# dc25-darknet-dialer-eaglev8.net
KiCad netlist of a schematic drawn in EAGLE
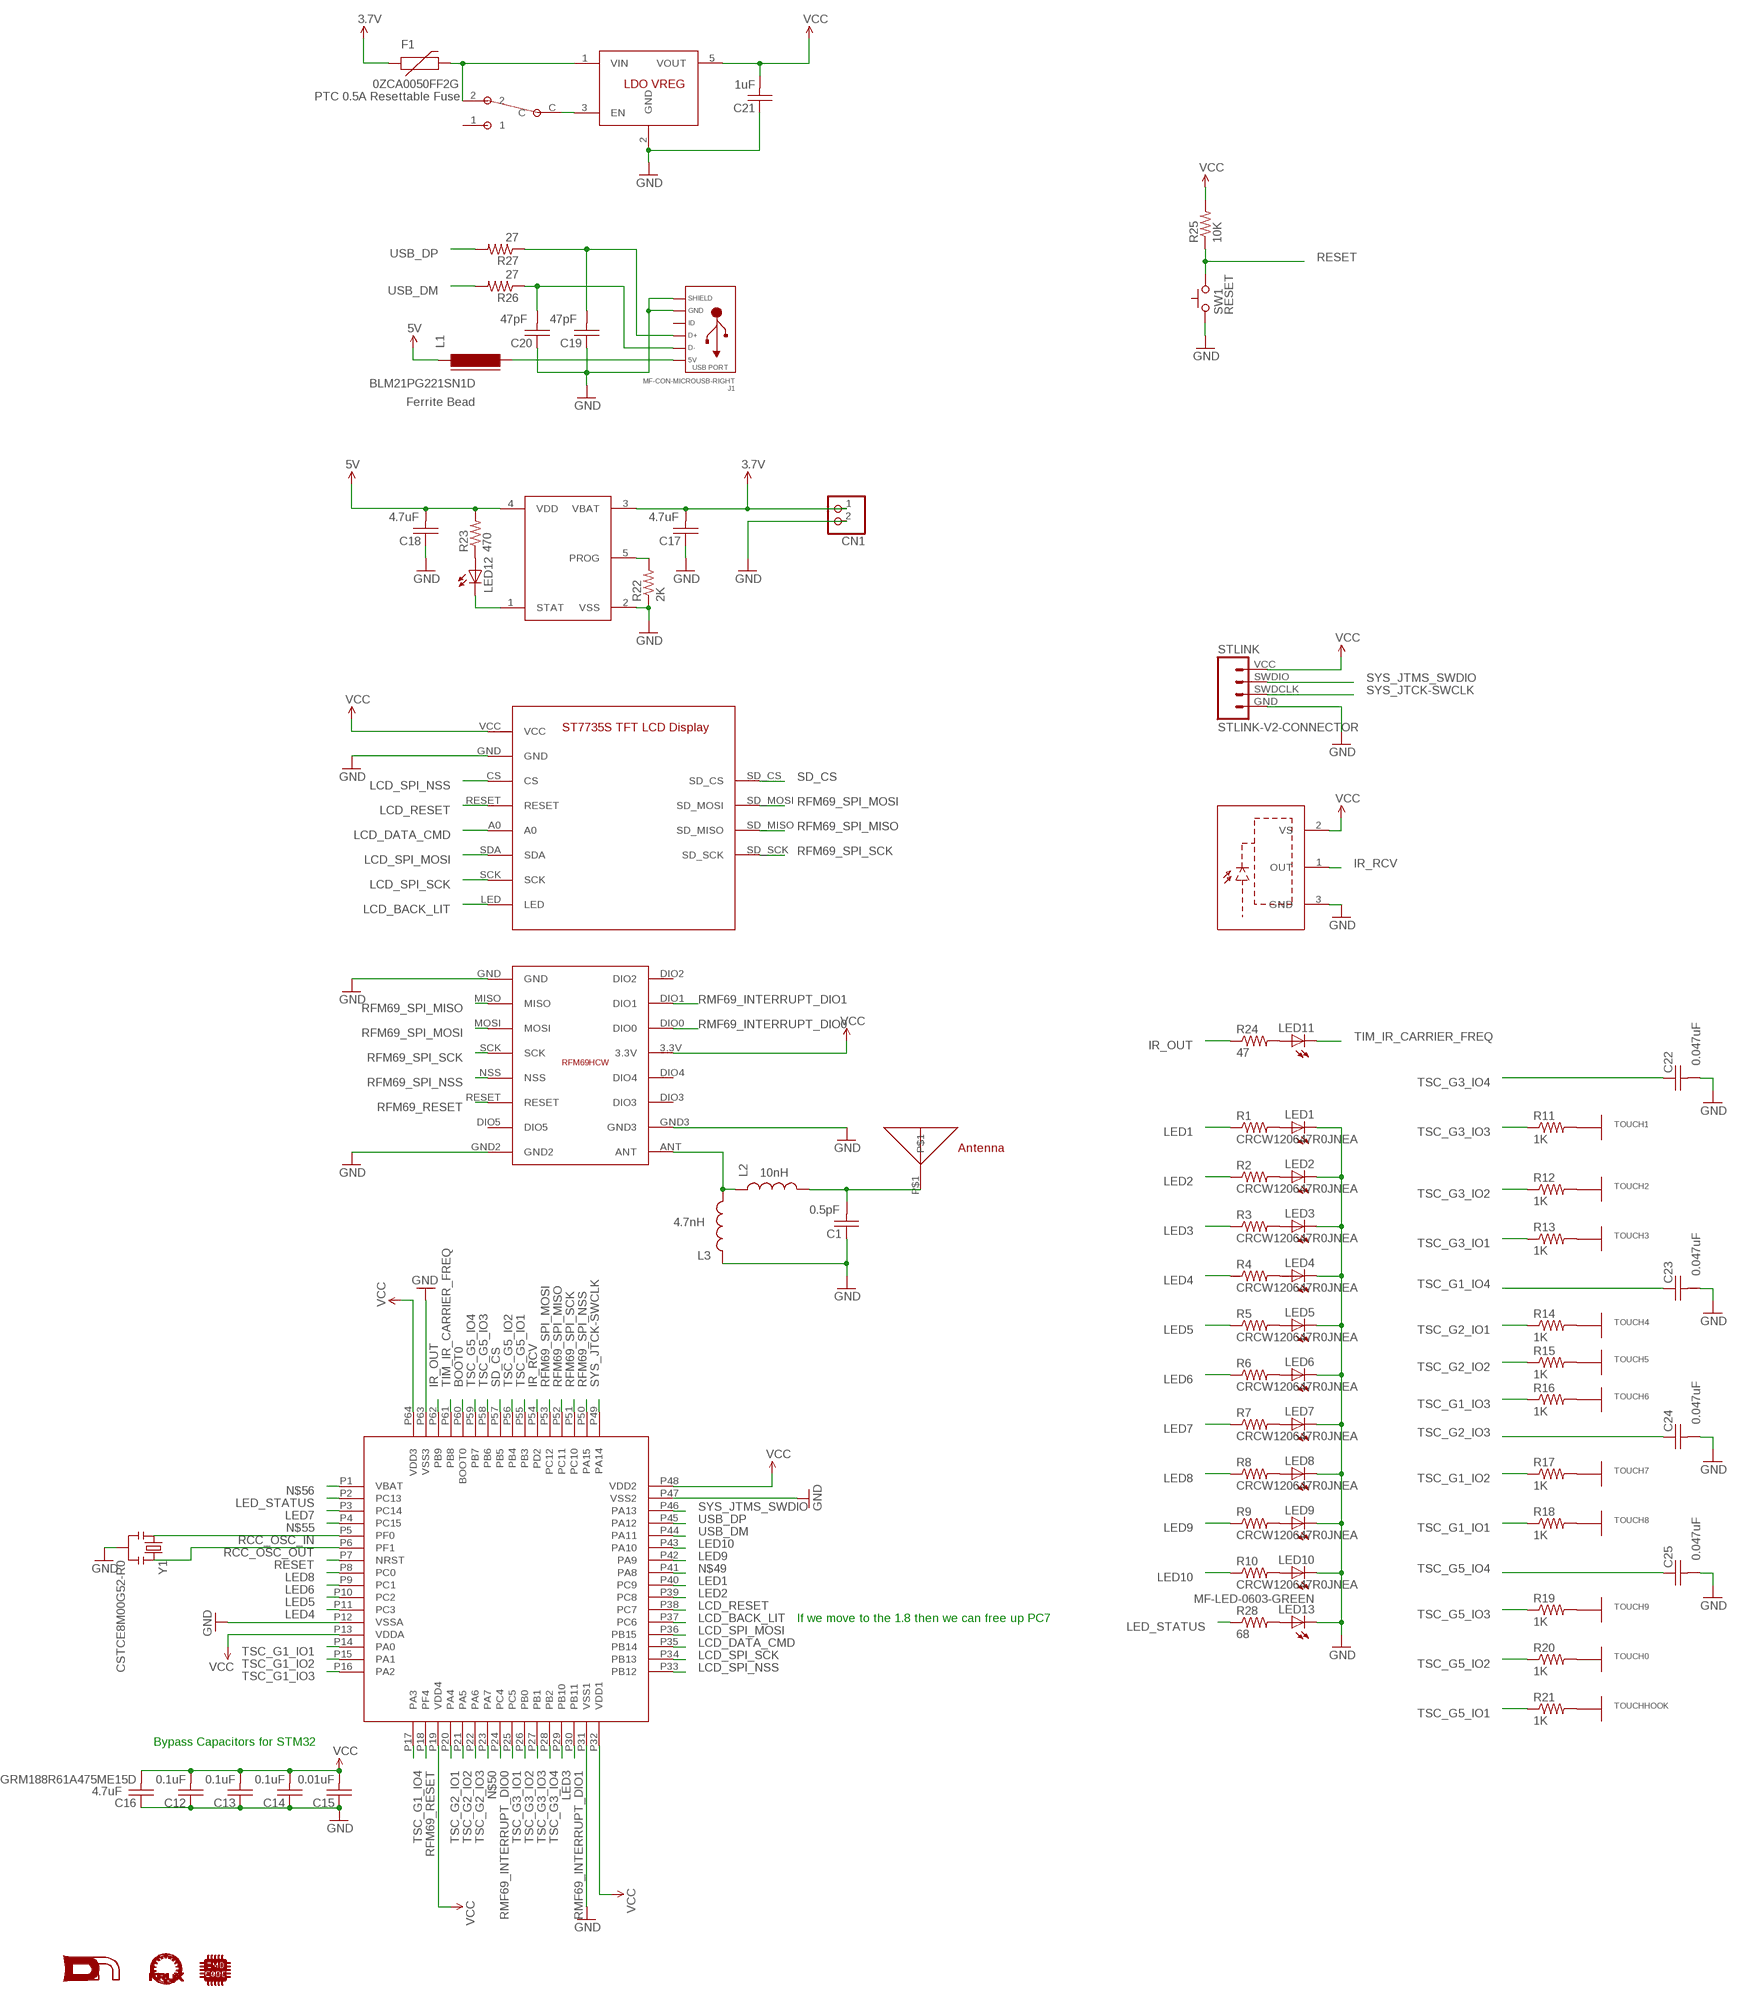
[diagram p0: schematic, sheet 1]

(export (version "E")
  (design (tool "Eeschema 10.0.6"))
  (components
    (comp (ref "C1")
      (value "251R14S0R5BV4T")
      (footprint "eagle-import:C0603")
      (libsource (lib "eagle-import") (part "C-USC0603"))
    )
    (comp (ref "C12")
      (value "0.1uF")
      (footprint "eagle-import:C0603")
      (libsource (lib "eagle-import") (part "C-USC0603"))
    )
    (comp (ref "C13")
      (value "0.1uF")
      (footprint "eagle-import:C0603")
      (libsource (lib "eagle-import") (part "C-USC0603"))
    )
    (comp (ref "C14")
      (value "0.1uF")
      (footprint "eagle-import:C0603")
      (libsource (lib "eagle-import") (part "C-USC0603"))
    )
    (comp (ref "C15")
      (value "0.01uF")
      (footprint "eagle-import:C0603")
      (libsource (lib "eagle-import") (part "C-USC0603"))
    )
    (comp (ref "C16")
      (value "GRM188R61A475ME15D")
      (footprint "eagle-import:C0603")
      (libsource (lib "eagle-import") (part "C-USC0603"))
    )
    (comp (ref "C17")
      (value "GRM188R61A475ME15D")
      (footprint "eagle-import:C0603")
      (libsource (lib "eagle-import") (part "C-USC0603"))
    )
    (comp (ref "C18")
      (value "GRM188R61A475ME15D")
      (footprint "eagle-import:C0603")
      (libsource (lib "eagle-import") (part "C-USC0603"))
    )
    (comp (ref "C19")
      (value "C0603C470J3GACTU")
      (footprint "eagle-import:C0603")
      (libsource (lib "eagle-import") (part "C-USC0603"))
    )
    (comp (ref "C20")
      (value "C0603C470J3GACTU")
      (footprint "eagle-import:C0603")
      (libsource (lib "eagle-import") (part "C-USC0603"))
    )
    (comp (ref "C21")
      (value "1uF")
      (footprint "eagle-import:C0603")
      (libsource (lib "eagle-import") (part "C-USC0603"))
    )
    (comp (ref "C22")
      (value "C0603C473J3RACAUTO")
      (footprint "eagle-import:C0603")
      (libsource (lib "eagle-import") (part "C-USC0603"))
    )
    (comp (ref "C23")
      (value "C0603C473J3RACAUTO")
      (footprint "eagle-import:C0603")
      (libsource (lib "eagle-import") (part "C-USC0603"))
    )
    (comp (ref "C24")
      (value "C0603C473J3RACAUTO")
      (footprint "eagle-import:C0603")
      (libsource (lib "eagle-import") (part "C-USC0603"))
    )
    (comp (ref "C25")
      (value "C0603C473J3RACAUTO")
      (footprint "eagle-import:C0603")
      (libsource (lib "eagle-import") (part "C-USC0603"))
    )
    (comp (ref "CN1")
      (value "JST_2PIN-THM-RA")
      (footprint "eagle-import:JST-PH-2-THM-RA")
      (libsource (lib "eagle-import") (part "JST_2PIN-THM-RA"))
    )
    (comp (ref "F1")
      (value "0ZCA0050FF2G")
      (footprint "eagle-import:PTC-1206")
      (libsource (lib "eagle-import") (part "PTCSMD"))
    )
    (comp (ref "J1")
      (value "MF-CON-MICROUSB-RIGHT")
      (footprint "eagle-import:MICROUSB-RIGHT")
      (fields (field (name "HOUSEPART") "YES"))
      (libsource (lib "eagle-import") (part "USB_MICRO_RIGHT"))
    )
    (comp (ref "L1")
      (value "BLM21PG221SN1D")
      (footprint "eagle-import:FB603")
      (libsource (lib "eagle-import") (part "FERRITE-0603"))
    )
    (comp (ref "L2")
      (value "CI160808-10NJ")
      (footprint "eagle-import:0603")
      (libsource (lib "eagle-import") (part "INDUCTOR0603"))
    )
    (comp (ref "L3")
      (value "CI160808-4N7D")
      (footprint "eagle-import:0603")
      (libsource (lib "eagle-import") (part "INDUCTOR0603"))
    )
    (comp (ref "LED1")
      (value "LEDREVERSEMOUNT")
      (footprint "eagle-import:GULLWING_LED")
      (libsource (lib "eagle-import") (part "LEDREVERSEMOUNT"))
    )
    (comp (ref "LED2")
      (value "LEDREVERSEMOUNT")
      (footprint "eagle-import:GULLWING_LED")
      (libsource (lib "eagle-import") (part "LEDREVERSEMOUNT"))
    )
    (comp (ref "LED3")
      (value "LEDREVERSEMOUNT")
      (footprint "eagle-import:GULLWING_LED")
      (libsource (lib "eagle-import") (part "LEDREVERSEMOUNT"))
    )
    (comp (ref "LED4")
      (value "LEDREVERSEMOUNT")
      (footprint "eagle-import:GULLWING_LED")
      (libsource (lib "eagle-import") (part "LEDREVERSEMOUNT"))
    )
    (comp (ref "LED5")
      (value "LEDREVERSEMOUNT")
      (footprint "eagle-import:GULLWING_LED")
      (libsource (lib "eagle-import") (part "LEDREVERSEMOUNT"))
    )
    (comp (ref "LED6")
      (value "LEDREVERSEMOUNT")
      (footprint "eagle-import:GULLWING_LED")
      (libsource (lib "eagle-import") (part "LEDREVERSEMOUNT"))
    )
    (comp (ref "LED7")
      (value "LEDREVERSEMOUNT")
      (footprint "eagle-import:GULLWING_LED")
      (libsource (lib "eagle-import") (part "LEDREVERSEMOUNT"))
    )
    (comp (ref "LED8")
      (value "LEDREVERSEMOUNT")
      (footprint "eagle-import:GULLWING_LED")
      (libsource (lib "eagle-import") (part "LEDREVERSEMOUNT"))
    )
    (comp (ref "LED9")
      (value "LEDREVERSEMOUNT")
      (footprint "eagle-import:GULLWING_LED")
      (libsource (lib "eagle-import") (part "LEDREVERSEMOUNT"))
    )
    (comp (ref "LED10")
      (value "LEDREVERSEMOUNT")
      (footprint "eagle-import:GULLWING_LED")
      (libsource (lib "eagle-import") (part "LEDREVERSEMOUNT"))
    )
    (comp (ref "LED11")
      (value "LED5MM")
      (footprint "eagle-import:LED5MM")
      (libsource (lib "eagle-import") (part "LED5MM"))
    )
    (comp (ref "LED12")
      (value "MF-LED-0603-GREEN")
      (footprint "eagle-import:LED-0603")
      (libsource (lib "eagle-import") (part "LED0603"))
    )
    (comp (ref "LED13")
      (value "MF-LED-0603-GREEN")
      (footprint "eagle-import:LED-0603")
      (libsource (lib "eagle-import") (part "LED0603"))
    )
    (comp (ref "R1")
      (value "CRCW120647R0JNEA")
      (footprint "eagle-import:1206")
      (libsource (lib "eagle-import") (part "RESISTOR1206"))
    )
    (comp (ref "R2")
      (value "CRCW120647R0JNEA")
      (footprint "eagle-import:1206")
      (libsource (lib "eagle-import") (part "RESISTOR1206"))
    )
    (comp (ref "R3")
      (value "CRCW120647R0JNEA")
      (footprint "eagle-import:1206")
      (libsource (lib "eagle-import") (part "RESISTOR1206"))
    )
    (comp (ref "R4")
      (value "CRCW120647R0JNEA")
      (footprint "eagle-import:1206")
      (libsource (lib "eagle-import") (part "RESISTOR1206"))
    )
    (comp (ref "R5")
      (value "CRCW120647R0JNEA")
      (footprint "eagle-import:1206")
      (libsource (lib "eagle-import") (part "RESISTOR1206"))
    )
    (comp (ref "R6")
      (value "CRCW120647R0JNEA")
      (footprint "eagle-import:1206")
      (libsource (lib "eagle-import") (part "RESISTOR1206"))
    )
    (comp (ref "R7")
      (value "CRCW120647R0JNEA")
      (footprint "eagle-import:1206")
      (libsource (lib "eagle-import") (part "RESISTOR1206"))
    )
    (comp (ref "R8")
      (value "CRCW120647R0JNEA")
      (footprint "eagle-import:1206")
      (libsource (lib "eagle-import") (part "RESISTOR1206"))
    )
    (comp (ref "R9")
      (value "CRCW120647R0JNEA")
      (footprint "eagle-import:1206")
      (libsource (lib "eagle-import") (part "RESISTOR1206"))
    )
    (comp (ref "R10")
      (value "CRCW120647R0JNEA")
      (footprint "eagle-import:1206")
      (libsource (lib "eagle-import") (part "RESISTOR1206"))
    )
    (comp (ref "R11")
      (value "1K")
      (footprint "eagle-import:0603-RES")
      (libsource (lib "eagle-import") (part "RESISTOR0603-RES"))
    )
    (comp (ref "R12")
      (value "1K")
      (footprint "eagle-import:0603-RES")
      (libsource (lib "eagle-import") (part "RESISTOR0603-RES"))
    )
    (comp (ref "R13")
      (value "1K")
      (footprint "eagle-import:0603-RES")
      (libsource (lib "eagle-import") (part "RESISTOR0603-RES"))
    )
    (comp (ref "R14")
      (value "1K")
      (footprint "eagle-import:0603-RES")
      (libsource (lib "eagle-import") (part "RESISTOR0603-RES"))
    )
    (comp (ref "R15")
      (value "1K")
      (footprint "eagle-import:0603-RES")
      (libsource (lib "eagle-import") (part "RESISTOR0603-RES"))
    )
    (comp (ref "R16")
      (value "1K")
      (footprint "eagle-import:0603-RES")
      (libsource (lib "eagle-import") (part "RESISTOR0603-RES"))
    )
    (comp (ref "R17")
      (value "1K")
      (footprint "eagle-import:0603-RES")
      (libsource (lib "eagle-import") (part "RESISTOR0603-RES"))
    )
    (comp (ref "R18")
      (value "1K")
      (footprint "eagle-import:0603-RES")
      (libsource (lib "eagle-import") (part "RESISTOR0603-RES"))
    )
    (comp (ref "R19")
      (value "1K")
      (footprint "eagle-import:0603-RES")
      (libsource (lib "eagle-import") (part "RESISTOR0603-RES"))
    )
    (comp (ref "R20")
      (value "1K")
      (footprint "eagle-import:0603-RES")
      (libsource (lib "eagle-import") (part "RESISTOR0603-RES"))
    )
    (comp (ref "R21")
      (value "1K")
      (footprint "eagle-import:0603-RES")
      (libsource (lib "eagle-import") (part "RESISTOR0603-RES"))
    )
    (comp (ref "R22")
      (value "2K")
      (footprint "eagle-import:0603-RES")
      (libsource (lib "eagle-import") (part "RESISTOR0603-RES"))
    )
    (comp (ref "R23")
      (value "470")
      (footprint "eagle-import:0603-RES")
      (libsource (lib "eagle-import") (part "RESISTOR0603-RES"))
    )
    (comp (ref "R24")
      (value "47")
      (footprint "eagle-import:0207_7")
      (libsource (lib "eagle-import") (part "R-US_0207/7"))
    )
    (comp (ref "R25")
      (value "10K")
      (footprint "eagle-import:0603-RES")
      (libsource (lib "eagle-import") (part "RESISTOR0603-RES"))
    )
    (comp (ref "R26")
      (value "27")
      (footprint "eagle-import:0603-RES")
      (libsource (lib "eagle-import") (part "RESISTOR0603-RES"))
    )
    (comp (ref "R27")
      (value "27")
      (footprint "eagle-import:0603-RES")
      (libsource (lib "eagle-import") (part "RESISTOR0603-RES"))
    )
    (comp (ref "R28")
      (value "68")
      (footprint "eagle-import:0603-RES")
      (libsource (lib "eagle-import") (part "RESISTOR0603-RES"))
    )
    (comp (ref "STLINK")
      (value "STLINK-V2-CONNECTOR")
      (footprint "eagle-import:1X04")
      (libsource (lib "eagle-import") (part "STLINK-V2-CONNECTOR"))
    )
    (comp (ref "SW1")
      (value "RESET")
      (footprint "eagle-import:TACTILE-2PIN-NARROW")
      (libsource (lib "eagle-import") (part "SWITCH_TACTILETACTILE-2PIN-NARROW"))
    )
    (comp (ref "TOUCH0")
      (value "CAP_TOUCH0")
      (footprint "eagle-import:CAP_TOUCH_PAD_0")
      (libsource (lib "eagle-import") (part "CAP_TOUCH0"))
    )
    (comp (ref "TOUCH1")
      (value "CAP_TOUCH1")
      (footprint "eagle-import:CAP_TOUCH_PAD_1")
      (libsource (lib "eagle-import") (part "CAP_TOUCH1"))
    )
    (comp (ref "TOUCH2")
      (value "CAP_TOUCH2")
      (footprint "eagle-import:CAP_TOUCH_PAD_2")
      (libsource (lib "eagle-import") (part "CAP_TOUCH2"))
    )
    (comp (ref "TOUCH3")
      (value "CAP_TOUCH3")
      (footprint "eagle-import:CAP_TOUCH_PAD_3")
      (libsource (lib "eagle-import") (part "CAP_TOUCH3"))
    )
    (comp (ref "TOUCH4")
      (value "CAP_TOUCH4")
      (footprint "eagle-import:CAP_TOUCH_PAD_4")
      (libsource (lib "eagle-import") (part "CAP_TOUCH4"))
    )
    (comp (ref "TOUCH5")
      (value "CAP_TOUCH5")
      (footprint "eagle-import:CAP_TOUCH_PAD_5")
      (libsource (lib "eagle-import") (part "CAP_TOUCH5"))
    )
    (comp (ref "TOUCH6")
      (value "CAP_TOUCH6")
      (footprint "eagle-import:CAP_TOUCH_PAD_6")
      (libsource (lib "eagle-import") (part "CAP_TOUCH6"))
    )
    (comp (ref "TOUCH7")
      (value "CAP_TOUCH7")
      (footprint "eagle-import:CAP_TOUCH_PAD_7")
      (libsource (lib "eagle-import") (part "CAP_TOUCH7"))
    )
    (comp (ref "TOUCH8")
      (value "CAP_TOUCH8")
      (footprint "eagle-import:CAP_TOUCH_PAD_8")
      (libsource (lib "eagle-import") (part "CAP_TOUCH8"))
    )
    (comp (ref "TOUCH9")
      (value "CAP_TOUCH9")
      (footprint "eagle-import:CAP_TOUCH_PAD_9")
      (libsource (lib "eagle-import") (part "CAP_TOUCH9"))
    )
    (comp (ref "TOUCHHOOK")
      (value "CAP_TOUCHHOOK")
      (footprint "eagle-import:CAP_TOUCH_PAD_HOOK")
      (libsource (lib "eagle-import") (part "CAP_TOUCHHOOK"))
    )
    (comp (ref "U$1")
      (value "DN_LOGO")
      (footprint "eagle-import:DN_LOGO")
      (libsource (lib "eagle-import") (part "DN_LOGO"))
    )
    (comp (ref "U$2")
      (value "STM32F302RBT6")
      (footprint "eagle-import:LQFP64")
      (libsource (lib "eagle-import") (part "STM32F302XC"))
    )
    (comp (ref "U$11")
      (value "SWITCH_SPDT")
      (footprint "eagle-import:SPDT_SSAJ120100")
      (libsource (lib "eagle-import") (part "SWITCH_SPDT"))
    )
    (comp (ref "U$12")
      (value "KRUX_LOGO")
      (footprint "eagle-import:KRUX_LOGO")
      (libsource (lib "eagle-import") (part "KRUX_LOGO"))
    )
    (comp (ref "U$15")
      (value "RFM69HCWRFN69HCWSMD")
      (footprint "eagle-import:16PIN-PCB-SMD")
      (libsource (lib "eagle-import") (part "RFM69HCWRFN69HCWSMD"))
    )
    (comp (ref "U$21")
      (value "0915AT43A0026E")
      (footprint "eagle-import:CHIP_ANTENNA_1.8X8MM")
      (libsource (lib "eagle-import") (part "CHIP_ANTENNA"))
    )
    (comp (ref "U$22")
      (value "ST7735S_LCD_MODULE")
      (footprint "eagle-import:ST7735S_LCD_DISPLAY")
      (libsource (lib "eagle-import") (part "ST7735S_LCD_MODULE"))
    )
    (comp (ref "U$23")
      (value "CMD_C0DE_LOGO")
      (footprint "eagle-import:CMD_C0DE_LOGO")
      (libsource (lib "eagle-import") (part "CMD_C0DE_LOGO"))
    )
    (comp (ref "U1")
      (value "BU33SD5WG-TR")
      (footprint "eagle-import:SOT23-5")
      (libsource (lib "eagle-import") (part "TLV702"))
    )
    (comp (ref "U2")
      (value "MCP73831T-5ACI/OT")
      (footprint "eagle-import:SOT23-5")
      (libsource (lib "eagle-import") (part "DS21984E"))
    )
    (comp (ref "U3")
      (value "SOP22FLAT")
      (footprint "eagle-import:IR-MODULE_FLAT")
      (libsource (lib "eagle-import") (part "SOP22FLAT"))
    )
    (comp (ref "Y1")
      (value "CSTCE8M00G52-R0")
      (footprint "eagle-import:RESONATOR-SMD")
      (libsource (lib "eagle-import") (part "RESONATORSMD"))
    )
  )
  (nets
    (net (code "1") (name "/BOOT0") (class "Default")
      (node (ref "U$2") (pin "P60") (pinfunction "BOOT0_P60") (pintype "bidirectional"))
    )
    (net (code "2") (name "/IR_OUT") (class "Default")
      (node (ref "R24") (pin "1") (pinfunction "1_1") (pintype "passive"))
      (node (ref "U$2") (pin "P62") (pinfunction "PB9_P62") (pintype "bidirectional"))
    )
    (net (code "3") (name "/IR_RCV") (class "Default")
      (node (ref "U$2") (pin "P54") (pinfunction "PD2_P54") (pintype "bidirectional"))
      (node (ref "U3") (pin "1") (pinfunction "OUT_1") (pintype "bidirectional"))
    )
    (net (code "4") (name "/LCD_BACK_LIT") (class "Default")
      (node (ref "U$2") (pin "P37") (pinfunction "PC6_P37") (pintype "bidirectional"))
      (node (ref "U$22") (pin "LED") (pinfunction "LED_LED") (pintype "bidirectional"))
    )
    (net (code "5") (name "/LCD_DATA_CMD") (class "Default")
      (node (ref "U$2") (pin "P35") (pinfunction "PB14_P35") (pintype "bidirectional"))
      (node (ref "U$22") (pin "A0") (pinfunction "A0_A0") (pintype "bidirectional"))
    )
    (net (code "6") (name "/LCD_RESET") (class "Default")
      (node (ref "U$2") (pin "P38") (pinfunction "PC7_P38") (pintype "bidirectional"))
      (node (ref "U$22") (pin "RESET") (pinfunction "RESET_RESET") (pintype "bidirectional"))
    )
    (net (code "7") (name "/LCD_SPI_MOSI") (class "Default")
      (node (ref "U$2") (pin "P36") (pinfunction "PB15_P36") (pintype "bidirectional"))
      (node (ref "U$22") (pin "SDA") (pinfunction "SDA_SDA") (pintype "bidirectional"))
    )
    (net (code "8") (name "/LCD_SPI_NSS") (class "Default")
      (node (ref "U$2") (pin "P33") (pinfunction "PB12_P33") (pintype "bidirectional"))
      (node (ref "U$22") (pin "CS") (pinfunction "CS_CS") (pintype "bidirectional"))
    )
    (net (code "9") (name "/LCD_SPI_SCK") (class "Default")
      (node (ref "U$2") (pin "P34") (pinfunction "PB13_P34") (pintype "bidirectional"))
      (node (ref "U$22") (pin "SCK") (pinfunction "SCK_SCK") (pintype "bidirectional"))
    )
    (net (code "10") (name "/LED1") (class "Default")
      (node (ref "R1") (pin "1") (pinfunction "1_1") (pintype "passive"))
      (node (ref "U$2") (pin "P40") (pinfunction "PC9_P40") (pintype "bidirectional"))
    )
    (net (code "11") (name "/LED2") (class "Default")
      (node (ref "R2") (pin "1") (pinfunction "1_1") (pintype "passive"))
      (node (ref "U$2") (pin "P39") (pinfunction "PC8_P39") (pintype "bidirectional"))
    )
    (net (code "12") (name "/LED3") (class "Default")
      (node (ref "R3") (pin "1") (pinfunction "1_1") (pintype "passive"))
      (node (ref "U$2") (pin "P29") (pinfunction "PB10_P29") (pintype "bidirectional"))
    )
    (net (code "13") (name "/LED4") (class "Default")
      (node (ref "R4") (pin "1") (pinfunction "1_1") (pintype "passive"))
      (node (ref "U$2") (pin "P11") (pinfunction "PC3_P11") (pintype "bidirectional"))
    )
    (net (code "14") (name "/LED5") (class "Default")
      (node (ref "R5") (pin "1") (pinfunction "1_1") (pintype "passive"))
      (node (ref "U$2") (pin "P10") (pinfunction "PC2_P10") (pintype "bidirectional"))
    )
    (net (code "15") (name "/LED6") (class "Default")
      (node (ref "R6") (pin "1") (pinfunction "1_1") (pintype "passive"))
      (node (ref "U$2") (pin "P9") (pinfunction "PC1_P9") (pintype "bidirectional"))
    )
    (net (code "16") (name "/LED7") (class "Default")
      (node (ref "R7") (pin "1") (pinfunction "1_1") (pintype "passive"))
      (node (ref "U$2") (pin "P3") (pinfunction "PC14_P3") (pintype "bidirectional"))
    )
    (net (code "17") (name "/LED8") (class "Default")
      (node (ref "R8") (pin "1") (pinfunction "1_1") (pintype "passive"))
      (node (ref "U$2") (pin "P8") (pinfunction "PC0_P8") (pintype "bidirectional"))
    )
    (net (code "18") (name "/LED9") (class "Default")
      (node (ref "R9") (pin "1") (pinfunction "1_1") (pintype "passive"))
      (node (ref "U$2") (pin "P42") (pinfunction "PA9_P42") (pintype "bidirectional"))
    )
    (net (code "19") (name "/LED10") (class "Default")
      (node (ref "R10") (pin "1") (pinfunction "1_1") (pintype "passive"))
      (node (ref "U$2") (pin "P43") (pinfunction "PA10_P43") (pintype "bidirectional"))
    )
    (net (code "20") (name "/LED_STATUS") (class "Default")
      (node (ref "R28") (pin "1") (pinfunction "1_1") (pintype "passive"))
      (node (ref "U$2") (pin "P2") (pinfunction "PC13_P2") (pintype "bidirectional"))
    )
    (net (code "21") (name "/N$49") (class "Default")
      (node (ref "U$2") (pin "P41") (pinfunction "PA8_P41") (pintype "bidirectional"))
    )
    (net (code "22") (name "/N$50") (class "Default")
      (node (ref "U$2") (pin "P23") (pinfunction "PA7_P23") (pintype "bidirectional"))
    )
    (net (code "23") (name "/N$55") (class "Default")
      (node (ref "U$2") (pin "P4") (pinfunction "PC15_P4") (pintype "bidirectional"))
    )
    (net (code "24") (name "/N$56") (class "Default")
      (node (ref "U$2") (pin "P1") (pinfunction "VBAT_P1") (pintype "bidirectional"))
    )
    (net (code "25") (name "/RCC_OSC_IN") (class "Default")
      (node (ref "U$2") (pin "P5") (pinfunction "PF0_P5") (pintype "bidirectional"))
      (node (ref "Y1") (pin "1") (pinfunction "1_1") (pintype "passive"))
    )
    (net (code "26") (name "/RCC_OSC_OUT") (class "Default")
      (node (ref "U$2") (pin "P6") (pinfunction "PF1_P6") (pintype "bidirectional"))
      (node (ref "Y1") (pin "3") (pinfunction "3_3") (pintype "passive"))
    )
    (net (code "27") (name "/RESET") (class "Default")
      (node (ref "R25") (pin "1") (pinfunction "1_1") (pintype "passive"))
      (node (ref "SW1") (pin "P$1") (pinfunction "A_P$1") (pintype "passive"))
      (node (ref "U$2") (pin "P7") (pinfunction "NRST_P7") (pintype "bidirectional"))
    )
    (net (code "28") (name "/RFM69_RESET") (class "Default")
      (node (ref "U$15") (pin "RESET") (pinfunction "RESET_RESET") (pintype "bidirectional"))
      (node (ref "U$2") (pin "P18") (pinfunction "PF4_P18") (pintype "bidirectional"))
    )
    (net (code "29") (name "/RFM69_SPI_MISO") (class "Default")
      (node (ref "U$15") (pin "MISO") (pinfunction "MISO_MISO") (pintype "bidirectional"))
      (node (ref "U$2") (pin "P52") (pinfunction "PC11_P52") (pintype "bidirectional"))
      (node (ref "U$22") (pin "SD_MISO") (pinfunction "SD_MISO_SD_MISO") (pintype "bidirectional"))
    )
    (net (code "30") (name "/RFM69_SPI_MOSI") (class "Default")
      (node (ref "U$15") (pin "MOSI") (pinfunction "MOSI_MOSI") (pintype "bidirectional"))
      (node (ref "U$2") (pin "P53") (pinfunction "PC12_P53") (pintype "bidirectional"))
      (node (ref "U$22") (pin "SD_MOSI") (pinfunction "SD_MOSI_SD_MOSI") (pintype "bidirectional"))
    )
    (net (code "31") (name "/RFM69_SPI_NSS") (class "Default")
      (node (ref "U$15") (pin "NSS") (pinfunction "NSS_NSS") (pintype "bidirectional"))
      (node (ref "U$2") (pin "P50") (pinfunction "PA15_P50") (pintype "bidirectional"))
    )
    (net (code "32") (name "/RFM69_SPI_SCK") (class "Default")
      (node (ref "U$15") (pin "SCK") (pinfunction "SCK_SCK") (pintype "bidirectional"))
      (node (ref "U$2") (pin "P51") (pinfunction "PC10_P51") (pintype "bidirectional"))
      (node (ref "U$22") (pin "SD_SCK") (pinfunction "SD_SCK_SD_SCK") (pintype "bidirectional"))
    )
    (net (code "33") (name "/RMF69_INTERRUPT_DIO0") (class "Default")
      (node (ref "U$15") (pin "DIO0") (pinfunction "DIO0_DIO0") (pintype "bidirectional"))
      (node (ref "U$2") (pin "P24") (pinfunction "PC4_P24") (pintype "bidirectional"))
    )
    (net (code "34") (name "/RMF69_INTERRUPT_DIO1") (class "Default")
      (node (ref "U$15") (pin "DIO1") (pinfunction "DIO1_DIO1") (pintype "bidirectional"))
      (node (ref "U$2") (pin "P30") (pinfunction "PB11_P30") (pintype "bidirectional"))
    )
    (net (code "35") (name "/SD_CS") (class "Default")
      (node (ref "U$2") (pin "P57") (pinfunction "PB5_P57") (pintype "bidirectional"))
      (node (ref "U$22") (pin "SD_CS") (pinfunction "SD_CS_SD_CS") (pintype "bidirectional"))
    )
    (net (code "36") (name "/SYS_JTCK-SWCLK") (class "Default")
      (node (ref "STLINK") (pin "SWDCLK") (pinfunction "SWDCLK_SWDCLK") (pintype "input"))
      (node (ref "U$2") (pin "P49") (pinfunction "PA14_P49") (pintype "bidirectional"))
    )
    (net (code "37") (name "/SYS_JTMS_SWDIO") (class "Default")
      (node (ref "STLINK") (pin "SWDIO") (pinfunction "SWDIO_SWDIO") (pintype "bidirectional"))
      (node (ref "U$2") (pin "P46") (pinfunction "PA13_P46") (pintype "bidirectional"))
    )
    (net (code "38") (name "/TIM_IR_CARRIER_FREQ") (class "Default")
      (node (ref "LED11") (pin "K") (pinfunction "C_K") (pintype "output"))
      (node (ref "U$2") (pin "P61") (pinfunction "PB8_P61") (pintype "bidirectional"))
    )
    (net (code "39") (name "/TSC_G1_IO1") (class "Default")
      (node (ref "R18") (pin "1") (pinfunction "1_1") (pintype "passive"))
      (node (ref "U$2") (pin "P14") (pinfunction "PA0_P14") (pintype "bidirectional"))
    )
    (net (code "40") (name "/TSC_G1_IO2") (class "Default")
      (node (ref "R17") (pin "1") (pinfunction "1_1") (pintype "passive"))
      (node (ref "U$2") (pin "P15") (pinfunction "PA1_P15") (pintype "bidirectional"))
    )
    (net (code "41") (name "/TSC_G1_IO3") (class "Default")
      (node (ref "R16") (pin "1") (pinfunction "1_1") (pintype "passive"))
      (node (ref "U$2") (pin "P16") (pinfunction "PA2_P16") (pintype "bidirectional"))
    )
    (net (code "42") (name "/TSC_G1_IO4") (class "Default")
      (node (ref "C23") (pin "1") (pinfunction "1_1") (pintype "passive"))
      (node (ref "U$2") (pin "P17") (pinfunction "PA3_P17") (pintype "bidirectional"))
    )
    (net (code "43") (name "/TSC_G2_IO1") (class "Default")
      (node (ref "R14") (pin "1") (pinfunction "1_1") (pintype "passive"))
      (node (ref "U$2") (pin "P20") (pinfunction "PA4_P20") (pintype "bidirectional"))
    )
    (net (code "44") (name "/TSC_G2_IO2") (class "Default")
      (node (ref "R15") (pin "1") (pinfunction "1_1") (pintype "passive"))
      (node (ref "U$2") (pin "P21") (pinfunction "PA5_P21") (pintype "bidirectional"))
    )
    (net (code "45") (name "/TSC_G2_IO3") (class "Default")
      (node (ref "C24") (pin "1") (pinfunction "1_1") (pintype "passive"))
      (node (ref "U$2") (pin "P22") (pinfunction "PA6_P22") (pintype "bidirectional"))
    )
    (net (code "46") (name "/TSC_G3_IO1") (class "Default")
      (node (ref "R13") (pin "1") (pinfunction "1_1") (pintype "passive"))
      (node (ref "U$2") (pin "P25") (pinfunction "PC5_P25") (pintype "bidirectional"))
    )
    (net (code "47") (name "/TSC_G3_IO2") (class "Default")
      (node (ref "R12") (pin "1") (pinfunction "1_1") (pintype "passive"))
      (node (ref "U$2") (pin "P26") (pinfunction "PB0_P26") (pintype "bidirectional"))
    )
    (net (code "48") (name "/TSC_G3_IO3") (class "Default")
      (node (ref "R11") (pin "1") (pinfunction "1_1") (pintype "passive"))
      (node (ref "U$2") (pin "P27") (pinfunction "PB1_P27") (pintype "bidirectional"))
    )
    (net (code "49") (name "/TSC_G3_IO4") (class "Default")
      (node (ref "C22") (pin "1") (pinfunction "1_1") (pintype "passive"))
      (node (ref "U$2") (pin "P28") (pinfunction "PB2_P28") (pintype "bidirectional"))
    )
    (net (code "50") (name "/TSC_G5_IO1") (class "Default")
      (node (ref "R21") (pin "1") (pinfunction "1_1") (pintype "passive"))
      (node (ref "U$2") (pin "P55") (pinfunction "PB3_P55") (pintype "bidirectional"))
    )
    (net (code "51") (name "/TSC_G5_IO2") (class "Default")
      (node (ref "R20") (pin "1") (pinfunction "1_1") (pintype "passive"))
      (node (ref "U$2") (pin "P56") (pinfunction "PB4_P56") (pintype "bidirectional"))
    )
    (net (code "52") (name "/TSC_G5_IO3") (class "Default")
      (node (ref "R19") (pin "1") (pinfunction "1_1") (pintype "passive"))
      (node (ref "U$2") (pin "P58") (pinfunction "PB6_P58") (pintype "bidirectional"))
    )
    (net (code "53") (name "/TSC_G5_IO4") (class "Default")
      (node (ref "C25") (pin "1") (pinfunction "1_1") (pintype "passive"))
      (node (ref "U$2") (pin "P59") (pinfunction "PB7_P59") (pintype "bidirectional"))
    )
    (net (code "54") (name "/USB_DM") (class "Default")
      (node (ref "R26") (pin "2") (pinfunction "2_2") (pintype "passive"))
      (node (ref "U$2") (pin "P44") (pinfunction "PA11_P44") (pintype "bidirectional"))
    )
    (net (code "55") (name "/USB_DP") (class "Default")
      (node (ref "R27") (pin "2") (pinfunction "2_2") (pintype "passive"))
      (node (ref "U$2") (pin "P45") (pinfunction "PA12_P45") (pintype "bidirectional"))
    )
    (net (code "56") (name "3.7V") (class "Default")
      (node (ref "C17") (pin "2") (pinfunction "2_2") (pintype "passive"))
      (node (ref "CN1") (pin "1") (pinfunction "2_1") (pintype "passive"))
      (node (ref "F1") (pin "1") (pinfunction "1_1") (pintype "bidirectional"))
      (node (ref "U2") (pin "3") (pinfunction "VBAT_3") (pintype "bidirectional"))
    )
    (net (code "57") (name "5V") (class "Default")
      (node (ref "C18") (pin "2") (pinfunction "2_2") (pintype "passive"))
      (node (ref "L1") (pin "1") (pinfunction "1_1") (pintype "passive"))
      (node (ref "R23") (pin "2") (pinfunction "2_2") (pintype "passive"))
      (node (ref "U2") (pin "4") (pinfunction "VDD_4") (pintype "bidirectional"))
    )
    (net (code "58") (name "GND") (class "Default")
      (node (ref "C1") (pin "1") (pinfunction "1_1") (pintype "passive"))
      (node (ref "C12") (pin "1") (pinfunction "1_1") (pintype "passive"))
      (node (ref "C13") (pin "1") (pinfunction "1_1") (pintype "passive"))
      (node (ref "C14") (pin "1") (pinfunction "1_1") (pintype "passive"))
      (node (ref "C15") (pin "1") (pinfunction "1_1") (pintype "passive"))
      (node (ref "C16") (pin "1") (pinfunction "1_1") (pintype "passive"))
      (node (ref "C17") (pin "1") (pinfunction "1_1") (pintype "passive"))
      (node (ref "C18") (pin "1") (pinfunction "1_1") (pintype "passive"))
      (node (ref "C19") (pin "1") (pinfunction "1_1") (pintype "passive"))
      (node (ref "C20") (pin "1") (pinfunction "1_1") (pintype "passive"))
      (node (ref "C21") (pin "1") (pinfunction "1_1") (pintype "passive"))
      (node (ref "C22") (pin "2") (pinfunction "2_2") (pintype "passive"))
      (node (ref "C23") (pin "2") (pinfunction "2_2") (pintype "passive"))
      (node (ref "C24") (pin "2") (pinfunction "2_2") (pintype "passive"))
      (node (ref "C25") (pin "2") (pinfunction "2_2") (pintype "passive"))
      (node (ref "CN1") (pin "2") (pinfunction "1_2") (pintype "passive"))
      (node (ref "J1") (pin "5") (pinfunction "GND_5") (pintype "power_in"))
      (node (ref "J1") (pin "S1") (pinfunction "SLD_S1") (pintype "power_in"))
      (node (ref "J1") (pin "S2") (pinfunction "SLD_S2") (pintype "power_in"))
      (node (ref "J1") (pin "S3") (pinfunction "SLD_S3") (pintype "power_in"))
      (node (ref "J1") (pin "S4") (pinfunction "SLD_S4") (pintype "power_in"))
      (node (ref "J1") (pin "S5") (pinfunction "SLD_S5") (pintype "power_in"))
      (node (ref "J1") (pin "S6") (pinfunction "SLD_S6") (pintype "power_in"))
      (node (ref "L3") (pin "1") (pinfunction "1_1") (pintype "passive"))
      (node (ref "LED1") (pin "C") (pinfunction "C_C") (pintype "output"))
      (node (ref "LED10") (pin "C") (pinfunction "C_C") (pintype "output"))
      (node (ref "LED13") (pin "C") (pinfunction "C_C") (pintype "output"))
      (node (ref "LED2") (pin "C") (pinfunction "C_C") (pintype "output"))
      (node (ref "LED3") (pin "C") (pinfunction "C_C") (pintype "output"))
      (node (ref "LED4") (pin "C") (pinfunction "C_C") (pintype "output"))
      (node (ref "LED5") (pin "C") (pinfunction "C_C") (pintype "output"))
      (node (ref "LED6") (pin "C") (pinfunction "C_C") (pintype "output"))
      (node (ref "LED7") (pin "C") (pinfunction "C_C") (pintype "output"))
      (node (ref "LED8") (pin "C") (pinfunction "C_C") (pintype "output"))
      (node (ref "LED9") (pin "C") (pinfunction "C_C") (pintype "output"))
      (node (ref "R22") (pin "1") (pinfunction "1_1") (pintype "passive"))
      (node (ref "STLINK") (pin "GND") (pinfunction "GND_GND") (pintype "power_in"))
      (node (ref "SW1") (pin "P$2") (pinfunction "C_P$2") (pintype "passive"))
      (node (ref "U$15") (pin "GND") (pinfunction "GND_GND") (pintype "bidirectional"))
      (node (ref "U$15") (pin "GND2") (pinfunction "GND2_GND2") (pintype "bidirectional"))
      (node (ref "U$15") (pin "GND3") (pinfunction "GND3_GND3") (pintype "bidirectional"))
      (node (ref "U$2") (pin "P12") (pinfunction "VSSA_P12") (pintype "bidirectional"))
      (node (ref "U$2") (pin "P31") (pinfunction "VSS1_P31") (pintype "bidirectional"))
      (node (ref "U$2") (pin "P47") (pinfunction "VSS2_P47") (pintype "bidirectional"))
      (node (ref "U$2") (pin "P63") (pinfunction "VSS3_P63") (pintype "bidirectional"))
      (node (ref "U$22") (pin "GND") (pinfunction "GND_GND") (pintype "bidirectional"))
      (node (ref "U1") (pin "2") (pinfunction "GND_2") (pintype "bidirectional"))
      (node (ref "U2") (pin "2") (pinfunction "VSS_2") (pintype "bidirectional"))
      (node (ref "U3") (pin "3") (pinfunction "GND_3") (pintype "bidirectional"))
      (node (ref "Y1") (pin "2") (pinfunction "2_2") (pintype "passive"))
    )
    (net (code "59") (name "Net-(C1-Pad2)") (class "Default")
      (node (ref "C1") (pin "2") (pinfunction "2_2") (pintype "passive"))
      (node (ref "L2") (pin "2") (pinfunction "2_2") (pintype "passive"))
      (node (ref "U$21") (pin "P$1") (pinfunction "P$1_P$1") (pintype "bidirectional"))
    )
    (net (code "60") (name "Net-(J1-5V)") (class "Default")
      (node (ref "J1") (pin "1") (pinfunction "5V_1") (pintype "power_in"))
      (node (ref "L1") (pin "2") (pinfunction "2_2") (pintype "passive"))
    )
    (net (code "61") (name "Net-(J1-D+)") (class "Default")
      (node (ref "C19") (pin "2") (pinfunction "2_2") (pintype "passive"))
      (node (ref "J1") (pin "3") (pinfunction "D+_3") (pintype "bidirectional"))
      (node (ref "R27") (pin "1") (pinfunction "1_1") (pintype "passive"))
    )
    (net (code "62") (name "Net-(J1-D-)") (class "Default")
      (node (ref "C20") (pin "2") (pinfunction "2_2") (pintype "passive"))
      (node (ref "J1") (pin "2") (pinfunction "D-_2") (pintype "bidirectional"))
      (node (ref "R26") (pin "1") (pinfunction "1_1") (pintype "passive"))
    )
    (net (code "63") (name "Net-(L2-Pad1)") (class "Default")
      (node (ref "L2") (pin "1") (pinfunction "1_1") (pintype "passive"))
      (node (ref "L3") (pin "2") (pinfunction "2_2") (pintype "passive"))
      (node (ref "U$15") (pin "ANT") (pinfunction "ANT_ANT") (pintype "bidirectional"))
    )
    (net (code "64") (name "Net-(LED1-PadA)") (class "Default")
      (node (ref "LED1") (pin "A") (pinfunction "A_A") (pintype "input"))
      (node (ref "R1") (pin "2") (pinfunction "2_2") (pintype "passive"))
    )
    (net (code "65") (name "Net-(LED2-PadA)") (class "Default")
      (node (ref "LED2") (pin "A") (pinfunction "A_A") (pintype "input"))
      (node (ref "R2") (pin "2") (pinfunction "2_2") (pintype "passive"))
    )
    (net (code "66") (name "Net-(LED3-PadA)") (class "Default")
      (node (ref "LED3") (pin "A") (pinfunction "A_A") (pintype "input"))
      (node (ref "R3") (pin "2") (pinfunction "2_2") (pintype "passive"))
    )
    (net (code "67") (name "Net-(LED4-PadA)") (class "Default")
      (node (ref "LED4") (pin "A") (pinfunction "A_A") (pintype "input"))
      (node (ref "R4") (pin "2") (pinfunction "2_2") (pintype "passive"))
    )
    (net (code "68") (name "Net-(LED5-PadA)") (class "Default")
      (node (ref "LED5") (pin "A") (pinfunction "A_A") (pintype "input"))
      (node (ref "R5") (pin "2") (pinfunction "2_2") (pintype "passive"))
    )
    (net (code "69") (name "Net-(LED6-PadA)") (class "Default")
      (node (ref "LED6") (pin "A") (pinfunction "A_A") (pintype "input"))
      (node (ref "R6") (pin "2") (pinfunction "2_2") (pintype "passive"))
    )
    (net (code "70") (name "Net-(LED7-PadA)") (class "Default")
      (node (ref "LED7") (pin "A") (pinfunction "A_A") (pintype "input"))
      (node (ref "R7") (pin "2") (pinfunction "2_2") (pintype "passive"))
    )
    (net (code "71") (name "Net-(LED8-PadA)") (class "Default")
      (node (ref "LED8") (pin "A") (pinfunction "A_A") (pintype "input"))
      (node (ref "R8") (pin "2") (pinfunction "2_2") (pintype "passive"))
    )
    (net (code "72") (name "Net-(LED9-PadA)") (class "Default")
      (node (ref "LED9") (pin "A") (pinfunction "A_A") (pintype "input"))
      (node (ref "R9") (pin "2") (pinfunction "2_2") (pintype "passive"))
    )
    (net (code "73") (name "Net-(LED10-PadA)") (class "Default")
      (node (ref "LED10") (pin "A") (pinfunction "A_A") (pintype "input"))
      (node (ref "R10") (pin "2") (pinfunction "2_2") (pintype "passive"))
    )
    (net (code "74") (name "Net-(LED11-PadA)") (class "Default")
      (node (ref "LED11") (pin "A") (pinfunction "A_A") (pintype "input"))
      (node (ref "R24") (pin "2") (pinfunction "2_2") (pintype "passive"))
    )
    (net (code "75") (name "Net-(LED12-PadA)") (class "Default")
      (node (ref "LED12") (pin "A") (pinfunction "A_A") (pintype "input"))
      (node (ref "R23") (pin "1") (pinfunction "1_1") (pintype "passive"))
    )
    (net (code "76") (name "Net-(LED13-PadA)") (class "Default")
      (node (ref "LED13") (pin "A") (pinfunction "A_A") (pintype "input"))
      (node (ref "R28") (pin "2") (pinfunction "2_2") (pintype "passive"))
    )
    (net (code "77") (name "Net-(TOUCH0-TOUCH)") (class "Default")
      (node (ref "R20") (pin "2") (pinfunction "2_2") (pintype "passive"))
      (node (ref "TOUCH0") (pin "PAD") (pinfunction "TOUCH_PAD") (pintype "bidirectional"))
    )
    (net (code "78") (name "Net-(TOUCH1-TOUCH)") (class "Default")
      (node (ref "R11") (pin "2") (pinfunction "2_2") (pintype "passive"))
      (node (ref "TOUCH1") (pin "PAD") (pinfunction "TOUCH_PAD") (pintype "bidirectional"))
    )
    (net (code "79") (name "Net-(TOUCH2-TOUCH)") (class "Default")
      (node (ref "R12") (pin "2") (pinfunction "2_2") (pintype "passive"))
      (node (ref "TOUCH2") (pin "PAD") (pinfunction "TOUCH_PAD") (pintype "bidirectional"))
    )
    (net (code "80") (name "Net-(TOUCH3-TOUCH)") (class "Default")
      (node (ref "R13") (pin "2") (pinfunction "2_2") (pintype "passive"))
      (node (ref "TOUCH3") (pin "PAD") (pinfunction "TOUCH_PAD") (pintype "bidirectional"))
    )
    (net (code "81") (name "Net-(TOUCH4-TOUCH)") (class "Default")
      (node (ref "R14") (pin "2") (pinfunction "2_2") (pintype "passive"))
      (node (ref "TOUCH4") (pin "PAD") (pinfunction "TOUCH_PAD") (pintype "bidirectional"))
    )
    (net (code "82") (name "Net-(TOUCH5-TOUCH)") (class "Default")
      (node (ref "R15") (pin "2") (pinfunction "2_2") (pintype "passive"))
      (node (ref "TOUCH5") (pin "PAD") (pinfunction "TOUCH_PAD") (pintype "bidirectional"))
    )
    (net (code "83") (name "Net-(TOUCH6-TOUCH)") (class "Default")
      (node (ref "R16") (pin "2") (pinfunction "2_2") (pintype "passive"))
      (node (ref "TOUCH6") (pin "PAD") (pinfunction "TOUCH_PAD") (pintype "bidirectional"))
    )
    (net (code "84") (name "Net-(TOUCH7-TOUCH)") (class "Default")
      (node (ref "R17") (pin "2") (pinfunction "2_2") (pintype "passive"))
      (node (ref "TOUCH7") (pin "PAD") (pinfunction "TOUCH_PAD") (pintype "bidirectional"))
    )
    (net (code "85") (name "Net-(TOUCH8-TOUCH)") (class "Default")
      (node (ref "R18") (pin "2") (pinfunction "2_2") (pintype "passive"))
      (node (ref "TOUCH8") (pin "PAD") (pinfunction "TOUCH_PAD") (pintype "bidirectional"))
    )
    (net (code "86") (name "Net-(TOUCH9-TOUCH)") (class "Default")
      (node (ref "R19") (pin "2") (pinfunction "2_2") (pintype "passive"))
      (node (ref "TOUCH9") (pin "PAD") (pinfunction "TOUCH_PAD") (pintype "bidirectional"))
    )
    (net (code "87") (name "Net-(TOUCHHOOK-TOUCH)") (class "Default")
      (node (ref "R21") (pin "2") (pinfunction "2_2") (pintype "passive"))
      (node (ref "TOUCHHOOK") (pin "P$1") (pinfunction "TOUCH_P$1") (pintype "bidirectional"))
    )
    (net (code "88") (name "Net-(U1-EN)") (class "Default")
      (node (ref "U$11") (pin "C") (pinfunction "C_C") (pintype "bidirectional"))
      (node (ref "U1") (pin "3") (pinfunction "EN_3") (pintype "bidirectional"))
    )
    (net (code "89") (name "Net-(U1-VIN)") (class "Default")
      (node (ref "F1") (pin "2") (pinfunction "2_2") (pintype "bidirectional"))
      (node (ref "U$11") (pin "2") (pinfunction "2_2") (pintype "bidirectional"))
      (node (ref "U1") (pin "1") (pinfunction "VIN_1") (pintype "bidirectional"))
    )
    (net (code "90") (name "Net-(U2-PROG)") (class "Default")
      (node (ref "R22") (pin "2") (pinfunction "2_2") (pintype "passive"))
      (node (ref "U2") (pin "5") (pinfunction "PROG_5") (pintype "bidirectional"))
    )
    (net (code "91") (name "Net-(U2-STAT)") (class "Default")
      (node (ref "LED12") (pin "C") (pinfunction "C_C") (pintype "output"))
      (node (ref "U2") (pin "1") (pinfunction "STAT_1") (pintype "bidirectional"))
    )
    (net (code "92") (name "VCC") (class "Default")
      (node (ref "C12") (pin "2") (pinfunction "2_2") (pintype "passive"))
      (node (ref "C13") (pin "2") (pinfunction "2_2") (pintype "passive"))
      (node (ref "C14") (pin "2") (pinfunction "2_2") (pintype "passive"))
      (node (ref "C15") (pin "2") (pinfunction "2_2") (pintype "passive"))
      (node (ref "C16") (pin "2") (pinfunction "2_2") (pintype "passive"))
      (node (ref "C21") (pin "2") (pinfunction "2_2") (pintype "passive"))
      (node (ref "R25") (pin "2") (pinfunction "2_2") (pintype "passive"))
      (node (ref "STLINK") (pin "VCC") (pinfunction "VCC_VCC") (pintype "power_in"))
      (node (ref "U$15") (pin "3.3V") (pinfunction "3.3V_3.3V") (pintype "bidirectional"))
      (node (ref "U$2") (pin "P13") (pinfunction "VDDA_P13") (pintype "bidirectional"))
      (node (ref "U$2") (pin "P19") (pinfunction "VDD4_P19") (pintype "bidirectional"))
      (node (ref "U$2") (pin "P32") (pinfunction "VDD1_P32") (pintype "bidirectional"))
      (node (ref "U$2") (pin "P48") (pinfunction "VDD2_P48") (pintype "bidirectional"))
      (node (ref "U$2") (pin "P64") (pinfunction "VDD3_P64") (pintype "bidirectional"))
      (node (ref "U$22") (pin "VCC") (pinfunction "VCC_VCC") (pintype "bidirectional"))
      (node (ref "U1") (pin "5") (pinfunction "VOUT_5") (pintype "bidirectional"))
      (node (ref "U3") (pin "2") (pinfunction "VS_2") (pintype "bidirectional"))
    )
    (net (code "93") (name "unconnected-(J1-ID-Pad4)") (class "Default")
      (node (ref "J1") (pin "4") (pinfunction "ID_4") (pintype "bidirectional"))
    )
    (net (code "94") (name "unconnected-(U$11-Pad1)") (class "Default")
      (node (ref "U$11") (pin "1") (pinfunction "1_1") (pintype "bidirectional"))
    )
    (net (code "95") (name "unconnected-(U$15-PadDIO2)") (class "Default")
      (node (ref "U$15") (pin "DIO2") (pinfunction "DIO2_DIO2") (pintype "bidirectional"))
    )
    (net (code "96") (name "unconnected-(U$15-PadDIO3)") (class "Default")
      (node (ref "U$15") (pin "DIO3") (pinfunction "DIO3_DIO3") (pintype "bidirectional"))
    )
    (net (code "97") (name "unconnected-(U$15-PadDIO4)") (class "Default")
      (node (ref "U$15") (pin "DIO4") (pinfunction "DIO4_DIO4") (pintype "bidirectional"))
    )
    (net (code "98") (name "unconnected-(U$15-PadDIO5)") (class "Default")
      (node (ref "U$15") (pin "DIO5") (pinfunction "DIO5_DIO5") (pintype "bidirectional"))
    )
  )
)
